# ADDITIONAL.net
KiCad netlist of a schematic drawn in Altium Designer
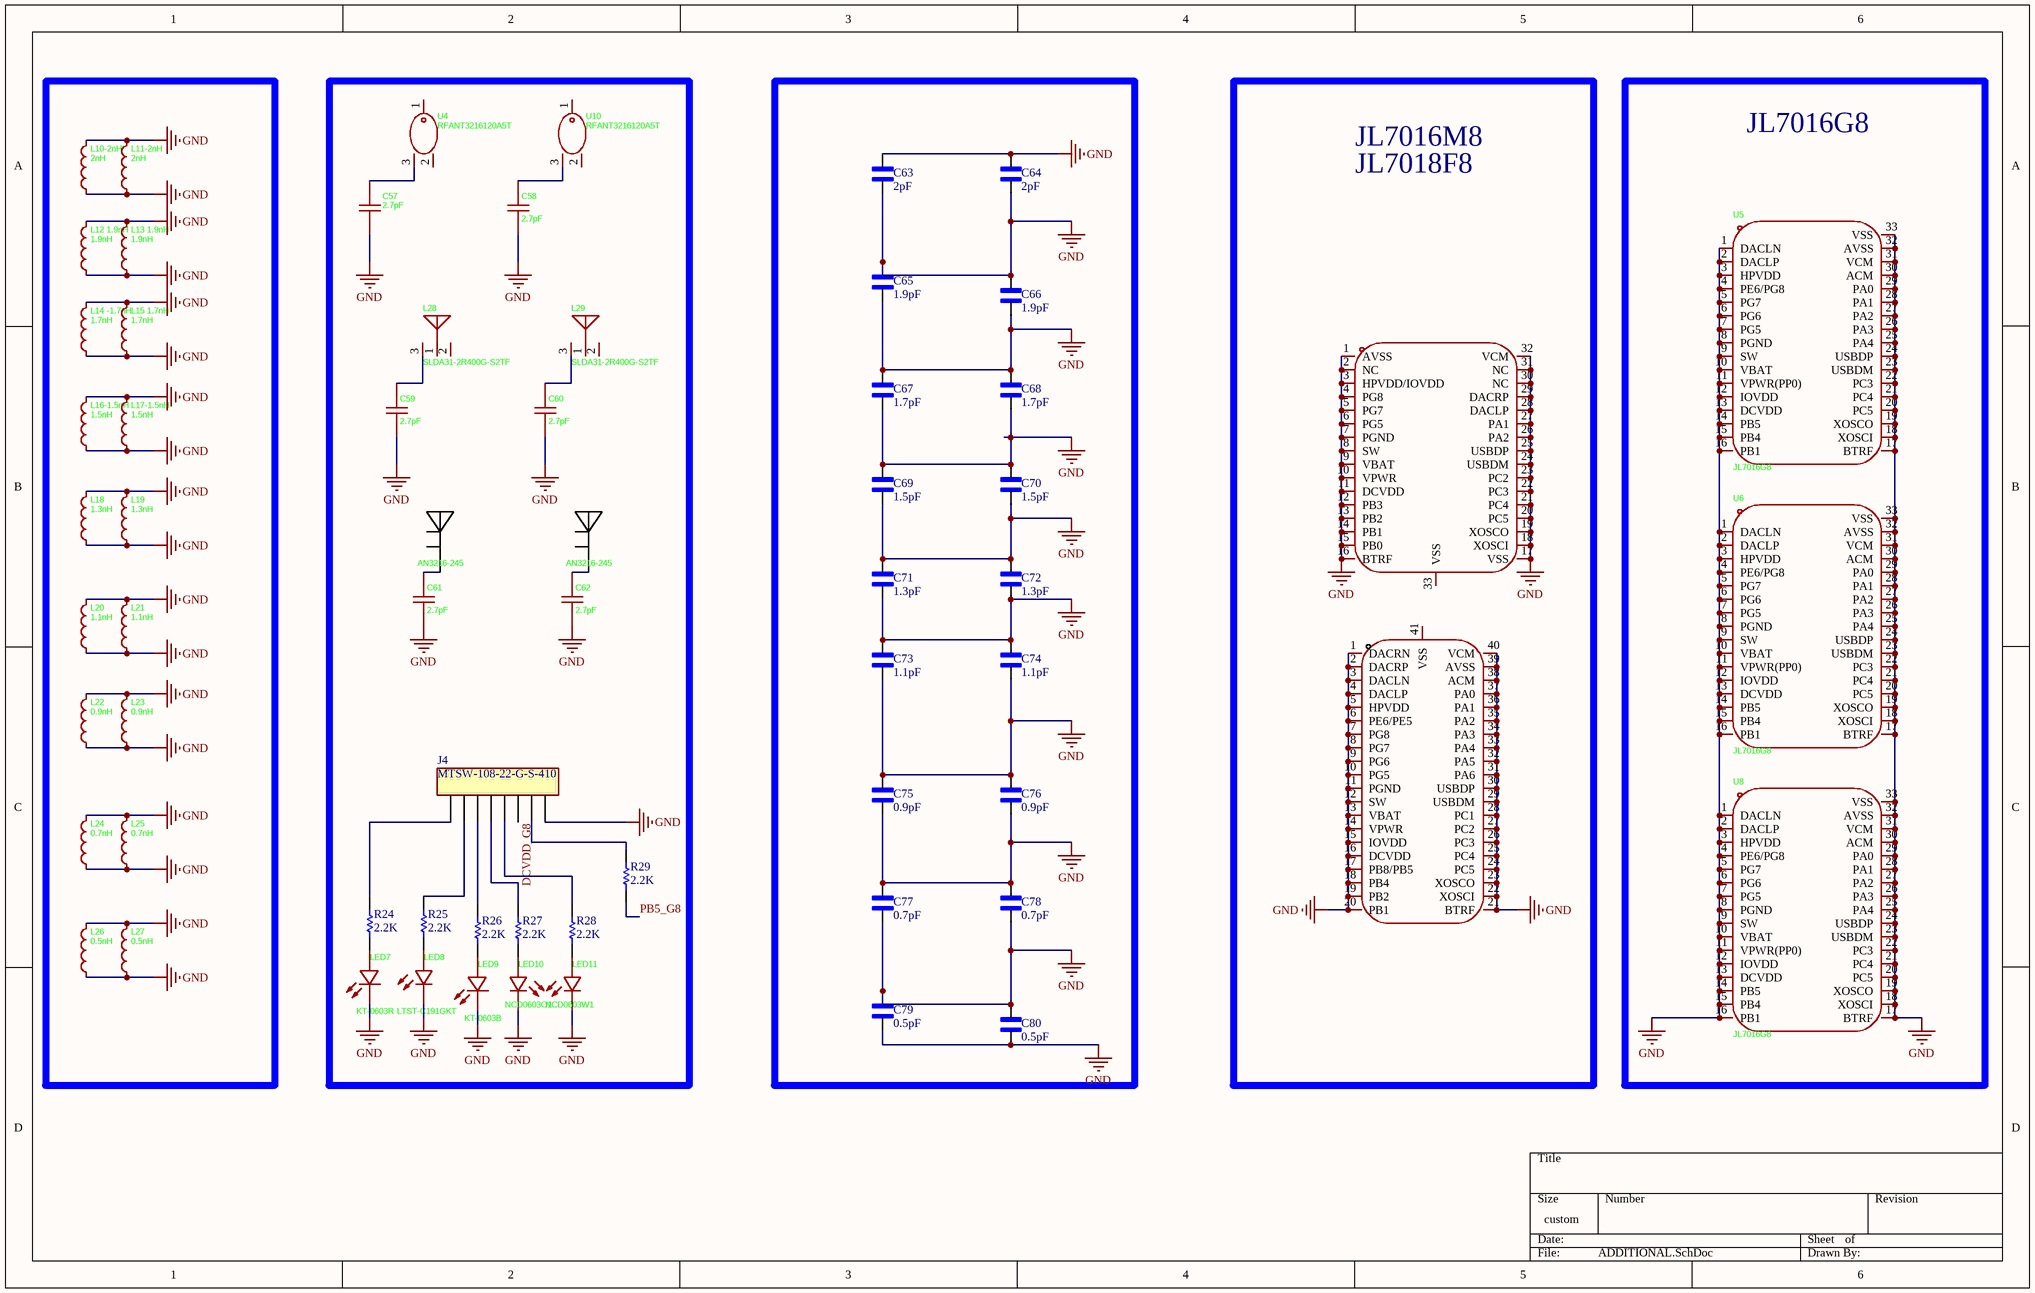
[diagram p0: ADDITIONAL.SchDoc]

(export (version "E")
  (design (tool "Eeschema 10.0.6"))
  (components
    (comp (ref "ANT4")
      (value "AN3216-245")
      (footprint "CUSTOME ANTEENA")
      (fields (field (name "MANUFACTURER") "Rainsun(霖昱微)") (field (name "POWER") "1W"))
      (libsource (lib "JEILI_DEV_BOARD") (part "AN3216-245"))
    )
    (comp (ref "ANT5")
      (value "AN3216-245")
      (footprint "CUSTOME ANTEENA")
      (fields (field (name "MANUFACTURER") "Rainsun(霖昱微)") (field (name "POWER") "1W"))
      (libsource (lib "JEILI_DEV_BOARD") (part "AN3216-245"))
    )
    (comp (ref "C57")
      (value "2.7pF")
      (footprint "C0603")
      (fields (field (name "MANUFACTURER") "FH(风华)") (field (name "MANUFACTURER PART") "0603CG2R7C500NT"))
      (libsource (lib "JEILI_DEV_BOARD") (part "0603CG2R7C500NT"))
    )
    (comp (ref "C58")
      (value "2.7pF")
      (footprint "C0603")
      (fields (field (name "MANUFACTURER") "FH(风华)") (field (name "MANUFACTURER PART") "0603CG2R7C500NT"))
      (libsource (lib "JEILI_DEV_BOARD") (part "0603CG2R7C500NT"))
    )
    (comp (ref "C59")
      (value "2.7pF")
      (footprint "C0603")
      (fields (field (name "MANUFACTURER") "FH(风华)") (field (name "MANUFACTURER PART") "0603CG2R7C500NT"))
      (libsource (lib "JEILI_DEV_BOARD") (part "0603CG2R7C500NT"))
    )
    (comp (ref "C60")
      (value "2.7pF")
      (footprint "C0603")
      (fields (field (name "MANUFACTURER") "FH(风华)") (field (name "MANUFACTURER PART") "0603CG2R7C500NT"))
      (libsource (lib "JEILI_DEV_BOARD") (part "0603CG2R7C500NT"))
    )
    (comp (ref "C61")
      (value "2.7pF")
      (footprint "C0603")
      (fields (field (name "MANUFACTURER") "FH(风华)") (field (name "MANUFACTURER PART") "0603CG2R7C500NT"))
      (libsource (lib "JEILI_DEV_BOARD") (part "0603CG2R7C500NT"))
    )
    (comp (ref "C62")
      (value "2.7pF")
      (footprint "C0603")
      (fields (field (name "MANUFACTURER") "FH(风华)") (field (name "MANUFACTURER PART") "0603CG2R7C500NT"))
      (libsource (lib "JEILI_DEV_BOARD") (part "0603CG2R7C500NT"))
    )
    (comp (ref "C63")
      (value "2pF")
      (footprint "C0402")
      (description "2pF 50V C0G 0402 Multilayer Ceramic Capacitors MLCC - SMD/SMT ROHS")
      (fields
        (field (name "MANUFACTURER") "Murata Electronics")
        (field (name "MFR.PART #") "GJM1555C1H2R0WB01D")
      )
      (libsource (lib "JEILI_DEV_BOARD") (part "CAP 2pF"))
    )
    (comp (ref "C64")
      (value "2pF")
      (footprint "C0402")
      (description "2pF 50V C0G 0402 Multilayer Ceramic Capacitors MLCC - SMD/SMT ROHS")
      (fields
        (field (name "MANUFACTURER") "Murata Electronics")
        (field (name "MFR.PART #") "GJM1555C1H2R0WB01D")
      )
      (libsource (lib "JEILI_DEV_BOARD") (part "CAP 2pF"))
    )
    (comp (ref "C65")
      (value "1.9pF")
      (footprint "C0402")
      (description "1.9pF 50V C0G 0402 Multilayer Ceramic Capacitors MLCC - SMD/SMT ROHS")
      (fields
        (field (name "MANUFACTURER") "Murata Electronics")
        (field (name "MFR.PART #") "GJM1555C1H1R9BB01D")
      )
      (libsource (lib "JEILI_DEV_BOARD") (part "CAP 1.9pF"))
    )
    (comp (ref "C66")
      (value "1.9pF")
      (footprint "C0402")
      (description "1.9pF 50V C0G 0402 Multilayer Ceramic Capacitors MLCC - SMD/SMT ROHS")
      (fields
        (field (name "MANUFACTURER") "Murata Electronics")
        (field (name "MFR.PART #") "GJM1555C1H1R9BB01D")
      )
      (libsource (lib "JEILI_DEV_BOARD") (part "CAP 1.9pF"))
    )
    (comp (ref "C67")
      (value "1.7pF")
      (footprint "C0402")
      (description "1.7pF 50V C0G 0402 Multilayer Ceramic Capacitors MLCC - SMD/SMT ROHS")
      (fields
        (field (name "MANUFACTURER") "Murata Electronics")
        (field (name "MFR.PART #") "GJM1555C1H1R7WB01D")
      )
      (libsource (lib "JEILI_DEV_BOARD") (part "CAP 1.7pF"))
    )
    (comp (ref "C68")
      (value "1.7pF")
      (footprint "C0402")
      (description "1.7pF 50V C0G 0402 Multilayer Ceramic Capacitors MLCC - SMD/SMT ROHS")
      (fields
        (field (name "MANUFACTURER") "Murata Electronics")
        (field (name "MFR.PART #") "GJM1555C1H1R7WB01D")
      )
      (libsource (lib "JEILI_DEV_BOARD") (part "CAP 1.7pF"))
    )
    (comp (ref "C69")
      (value "1.5pF")
      (footprint "C0402")
      (description "1.5pF 50V C0G 0402 Multilayer Ceramic Capacitors MLCC - SMD/SMT ROHS")
      (fields
        (field (name "MANUFACTURER") "Murata Electronics")
        (field (name "MFR.PART #") "GJM1555C1H1R5BB01D")
      )
      (libsource (lib "JEILI_DEV_BOARD") (part "CAP 1.5pF"))
    )
    (comp (ref "C70")
      (value "1.5pF")
      (footprint "C0402")
      (description "1.5pF 50V C0G 0402 Multilayer Ceramic Capacitors MLCC - SMD/SMT ROHS")
      (fields
        (field (name "MANUFACTURER") "Murata Electronics")
        (field (name "MFR.PART #") "GJM1555C1H1R5BB01D")
      )
      (libsource (lib "JEILI_DEV_BOARD") (part "CAP 1.5pF"))
    )
    (comp (ref "C71")
      (value "1.3pF")
      (footprint "C0402")
      (description "1.3pF 50V C0G 0402 Multilayer Ceramic Capacitors MLCC - SMD/SMT ROHS")
      (fields
        (field (name "MANUFACTURER") "Murata Electronics")
        (field (name "MFR.PART #") "GJM1555C1H1R3WB01D")
      )
      (libsource (lib "JEILI_DEV_BOARD") (part "CAP 1.3pF"))
    )
    (comp (ref "C72")
      (value "1.3pF")
      (footprint "C0402")
      (description "1.3pF 50V C0G 0402 Multilayer Ceramic Capacitors MLCC - SMD/SMT ROHS")
      (fields
        (field (name "MANUFACTURER") "Murata Electronics")
        (field (name "MFR.PART #") "GJM1555C1H1R3WB01D")
      )
      (libsource (lib "JEILI_DEV_BOARD") (part "CAP 1.3pF"))
    )
    (comp (ref "C73")
      (value "1.1pF")
      (footprint "C0402")
      (description "1.1pF 50V C0G 0402 Multilayer Ceramic Capacitors MLCC - SMD/SMT ROHS")
      (fields
        (field (name "MANUFACTURER") "Murata Electronics")
        (field (name "MFR.PART #") "GJM1555C1H1R1WB01D")
      )
      (libsource (lib "JEILI_DEV_BOARD") (part "CAP 1.1pF"))
    )
    (comp (ref "C74")
      (value "1.1pF")
      (footprint "C0402")
      (description "1.1pF 50V C0G 0402 Multilayer Ceramic Capacitors MLCC - SMD/SMT ROHS")
      (fields
        (field (name "MANUFACTURER") "Murata Electronics")
        (field (name "MFR.PART #") "GJM1555C1H1R1WB01D")
      )
      (libsource (lib "JEILI_DEV_BOARD") (part "CAP 1.1pF"))
    )
    (comp (ref "C75")
      (value "0.9pF")
      (footprint "C0402")
      (description "0.9pF 50V C0G 0402 Multilayer Ceramic Capacitors MLCC - SMD/SMT ROHS")
      (fields
        (field (name "MANUFACTURER") "FH (Guangdong Fenghua Advanced Tech)")
        (field (name "MFR.PART #") "0402CG0R9B500NT")
      )
      (libsource (lib "JEILI_DEV_BOARD") (part "CAP 0.9pF"))
    )
    (comp (ref "C76")
      (value "0.9pF")
      (footprint "C0402")
      (description "0.9pF 50V C0G 0402 Multilayer Ceramic Capacitors MLCC - SMD/SMT ROHS")
      (fields
        (field (name "MANUFACTURER") "FH (Guangdong Fenghua Advanced Tech)")
        (field (name "MFR.PART #") "0402CG0R9B500NT")
      )
      (libsource (lib "JEILI_DEV_BOARD") (part "CAP 0.9pF"))
    )
    (comp (ref "C77")
      (value "0.7pF")
      (footprint "C0402")
      (description "0.7pF 50V C0G 0402 Multilayer Ceramic Capacitors MLCC - SMD/SMT ROHS")
      (fields
        (field (name "MANUFACTURER") "FH (Guangdong Fenghua Advanced Tech)")
        (field (name "MFR.PART #") "0402CG0R7C500NT")
      )
      (libsource (lib "JEILI_DEV_BOARD") (part "CAP 0.7pF"))
    )
    (comp (ref "C78")
      (value "0.7pF")
      (footprint "C0402")
      (description "0.7pF 50V C0G 0402 Multilayer Ceramic Capacitors MLCC - SMD/SMT ROHS")
      (fields
        (field (name "MANUFACTURER") "FH (Guangdong Fenghua Advanced Tech)")
        (field (name "MFR.PART #") "0402CG0R7C500NT")
      )
      (libsource (lib "JEILI_DEV_BOARD") (part "CAP 0.7pF"))
    )
    (comp (ref "C79")
      (value "0.5pF")
      (footprint "C0402")
      (description "0.5pF 50V C0G 0402 Multilayer Ceramic Capacitors MLCC - SMD/SMT ROHS")
      (fields
        (field (name "MANUFACTURER") "FH (Guangdong Fenghua Advanced Tech)")
        (field (name "MFR.PART #") "0402CG0R5C500NT")
      )
      (libsource (lib "JEILI_DEV_BOARD") (part "CAP 0.5pF"))
    )
    (comp (ref "C80")
      (value "0.5pF")
      (footprint "C0402")
      (description "0.5pF 50V C0G 0402 Multilayer Ceramic Capacitors MLCC - SMD/SMT ROHS")
      (fields
        (field (name "MANUFACTURER") "FH (Guangdong Fenghua Advanced Tech)")
        (field (name "MFR.PART #") "0402CG0R5C500NT")
      )
      (libsource (lib "JEILI_DEV_BOARD") (part "CAP 0.5pF"))
    )
    (comp (ref "J4")
      (value "MTSW-108-22-G-S-410")
      (footprint "SAMTEC_MTSW-108-22-G-S-410")
      (libsource (lib "JEILI_DEV_BOARD") (part "MTSW-108-22-G-S-410"))
    )
    (comp (ref "L10-2nH")
      (value "2nH")
      (footprint "L0603")
      (description "2nH Multilayer inductor 0603 Inductors (SMD) ROHS")
      (fields
        (field (name "MANUFACTURER") "Murata Electronics")
        (field (name "MANUFACTURER PART") "SDCL1608C2N0STDF")
      )
      (libsource (lib "JEILI_DEV_BOARD") (part "2nH"))
    )
    (comp (ref "L11-2nH")
      (value "2nH")
      (footprint "L0603")
      (description "2nH Multilayer inductor 0603 Inductors (SMD) ROHS")
      (fields
        (field (name "MANUFACTURER") "Murata Electronics")
        (field (name "MANUFACTURER PART") "SDCL1608C2N0STDF")
      )
      (libsource (lib "JEILI_DEV_BOARD") (part "2nH"))
    )
    (comp (ref "L12 1.9nH")
      (value "1.9nH")
      (footprint "L0603")
      (description "1.04A 1.9nH 11.3MHz 16@250MHz 70mΩ 0402 Inductors (SMD) ROHS")
      (fields
        (field (name "MANUFACTURER") "Chilisin Elec")
        (field (name "MANUFACTURER PART") "CS0402-1N9B-S")
      )
      (libsource (lib "JEILI_DEV_BOARD") (part "1.9nH"))
    )
    (comp (ref "L13 1.9nH")
      (value "1.9nH")
      (footprint "L0603")
      (description "1.04A 1.9nH 11.3MHz 16@250MHz 70mΩ 0402 Inductors (SMD) ROHS")
      (fields
        (field (name "MANUFACTURER") "Chilisin Elec")
        (field (name "MANUFACTURER PART") "CS0402-1N9B-S")
      )
      (libsource (lib "JEILI_DEV_BOARD") (part "1.9nH"))
    )
    (comp (ref "L14 -1.7nH")
      (value "1.7nH")
      (footprint "L0603")
      (description "1.7nH 100mΩ 640mA 0402 Inductors (SMD) ROHS")
      (fields (field (name "MANUFACTURER") "Sunlord") (field (name "MANUFACTURER PART") "MWSD1005C1N7STM01"))
      (libsource (lib "JEILI_DEV_BOARD") (part "1.7nH"))
    )
    (comp (ref "L15 1.7nH")
      (value "1.7nH")
      (footprint "L0603")
      (description "1.7nH 100mΩ 640mA 0402 Inductors (SMD) ROHS")
      (fields (field (name "MANUFACTURER") "Sunlord") (field (name "MANUFACTURER PART") "MWSD1005C1N7STM01"))
      (libsource (lib "JEILI_DEV_BOARD") (part "1.7nH"))
    )
    (comp (ref "L16-1.5nH")
      (value "1.5nH")
      (footprint "L0603")
      (description "1.5nH 100mΩ 500mA 6GHz 8@100MHz Multilayer inductor 0603 Inductors (SMD) ROHS")
      (fields (field (name "MANUFACTURER") "Sunlord") (field (name "MANUFACTURER PART") "SDCL1608C1N5STDF"))
      (libsource (lib "JEILI_DEV_BOARD") (part "1.5nH"))
    )
    (comp (ref "L17-1.5nH")
      (value "1.5nH")
      (footprint "L0603")
      (description "1.5nH 100mΩ 500mA 6GHz 8@100MHz Multilayer inductor 0603 Inductors (SMD) ROHS")
      (fields (field (name "MANUFACTURER") "Sunlord") (field (name "MANUFACTURER PART") "SDCL1608C1N5STDF"))
      (libsource (lib "JEILI_DEV_BOARD") (part "1.5nH"))
    )
    (comp (ref "L18")
      (value "1.3nH")
      (footprint "L0603")
      (description "1.3nH 1A 40mΩ 7@100MHz 8GHz Multilayer inductor 0402 Inductors (SMD) ROHS")
      (fields (field (name "MANUFACTURER") "TDK") (field (name "MANUFACTURER PART") "MLG1005S1N3BT000"))
      (libsource (lib "JEILI_DEV_BOARD") (part "1.3nH"))
    )
    (comp (ref "L19")
      (value "1.3nH")
      (footprint "L0603")
      (description "1.3nH 1A 40mΩ 7@100MHz 8GHz Multilayer inductor 0402 Inductors (SMD) ROHS")
      (fields (field (name "MANUFACTURER") "TDK") (field (name "MANUFACTURER PART") "MLG1005S1N3BT000"))
      (libsource (lib "JEILI_DEV_BOARD") (part "1.3nH"))
    )
    (comp (ref "L20")
      (value "1.1nH")
      (footprint "L0603")
      (description "1.1nH 10GHz 1A 30mΩ 7@100MHz AEC-Q200 Multilayer inductor 0402 Inductors (SMD) ROHS")
      (fields (field (name "MANUFACTURER") "TDK") (field (name "MANUFACTURER PART") "MLG1005S1N1BTD25"))
      (libsource (lib "JEILI_DEV_BOARD") (part "1.1nH"))
    )
    (comp (ref "L21")
      (value "1.1nH")
      (footprint "L0603")
      (description "1.1nH 10GHz 1A 30mΩ 7@100MHz AEC-Q200 Multilayer inductor 0402 Inductors (SMD) ROHS")
      (fields (field (name "MANUFACTURER") "TDK") (field (name "MANUFACTURER PART") "MLG1005S1N1BTD25"))
      (libsource (lib "JEILI_DEV_BOARD") (part "1.1nH"))
    )
    (comp (ref "L22")
      (value "0.9nH")
      (footprint "L0603")
      (description "0.9nH 100mΩ 10GHz 1A Multilayer inductor 0402 Inductors (SMD) ROHS")
      (fields (field (name "MANUFACTURER") "TDK") (field (name "MANUFACTURER PART") "MLG1005S0N9BT000"))
      (libsource (lib "JEILI_DEV_BOARD") (part "0.9nH"))
    )
    (comp (ref "L23")
      (value "0.9nH")
      (footprint "L0603")
      (description "0.9nH 100mΩ 10GHz 1A Multilayer inductor 0402 Inductors (SMD) ROHS")
      (fields (field (name "MANUFACTURER") "TDK") (field (name "MANUFACTURER PART") "MLG1005S0N9BT000"))
      (libsource (lib "JEILI_DEV_BOARD") (part "0.9nH"))
    )
    (comp (ref "L24")
      (value "0.7nH")
      (footprint "L0603")
      (description "0.7nH 100mΩ 10GHz 1A Multilayer inductor 0402 Inductors (SMD) ROHS")
      (fields (field (name "MANUFACTURER") "TDK") (field (name "MANUFACTURER PART") "MLG1005S0N7BT000"))
      (libsource (lib "JEILI_DEV_BOARD") (part "0.7nH"))
    )
    (comp (ref "L25")
      (value "0.7nH")
      (footprint "L0603")
      (description "0.7nH 100mΩ 10GHz 1A Multilayer inductor 0402 Inductors (SMD) ROHS")
      (fields (field (name "MANUFACTURER") "TDK") (field (name "MANUFACTURER PART") "MLG1005S0N7BT000"))
      (libsource (lib "JEILI_DEV_BOARD") (part "0.7nH"))
    )
    (comp (ref "L26")
      (value "0.5nH")
      (footprint "L0603")
      (description "0.5nH 100mΩ 10GHz 1A Multilayer inductor 0402 Inductors (SMD) ROHS")
      (fields (field (name "MANUFACTURER") "TDK") (field (name "MANUFACTURER PART") "MLG1005S0N5BT000"))
      (libsource (lib "JEILI_DEV_BOARD") (part "0.5nH"))
    )
    (comp (ref "L27")
      (value "0.5nH")
      (footprint "L0603")
      (description "0.5nH 100mΩ 10GHz 1A Multilayer inductor 0402 Inductors (SMD) ROHS")
      (fields (field (name "MANUFACTURER") "TDK") (field (name "MANUFACTURER PART") "MLG1005S0N5BT000"))
      (libsource (lib "JEILI_DEV_BOARD") (part "0.5nH"))
    )
    (comp (ref "L28")
      (value "SLDA31-2R400G-S2TF")
      (footprint "CUSTOME ANTEENA")
      (fields (field (name "MANUFACTURER") "Sunlord(顺络)") (field (name "POWER") "3W"))
      (libsource (lib "JEILI_DEV_BOARD") (part "SLDA31-2R400G-S2TF"))
    )
    (comp (ref "L29")
      (value "SLDA31-2R400G-S2TF")
      (footprint "CUSTOME ANTEENA")
      (fields (field (name "MANUFACTURER") "Sunlord(顺络)") (field (name "POWER") "3W"))
      (libsource (lib "JEILI_DEV_BOARD") (part "SLDA31-2R400G-S2TF"))
    )
    (comp (ref "LED7")
      (value "KT-0603R")
      (footprint "LED0603-RD")
      (fields (field (name "MANUFACTURER") "KENTO"))
      (libsource (lib "JEILI_DEV_BOARD") (part "KT-0603R"))
    )
    (comp (ref "LED8")
      (value "LTST-C191GKT")
      (footprint "LED0603-R-RD_GREEN")
      (fields (field (name "MANUFACTURER") "LITEON(光宝)"))
      (libsource (lib "JEILI_DEV_BOARD") (part "LTST-C191GKT"))
    )
    (comp (ref "LED9")
      (value "KT-0603B")
      (footprint "LED0603-RD")
      (fields (field (name "MANUFACTURER") "KENTO"))
      (libsource (lib "JEILI_DEV_BOARD") (part "KT-0603B"))
    )
    (comp (ref "LED10")
      (value "NCD0603O1")
      (footprint "LED0603-RD")
      (fields (field (name "MANUFACTURER") "国星光电"))
      (libsource (lib "JEILI_DEV_BOARD") (part "NCD0603O1"))
    )
    (comp (ref "LED11")
      (value "NCD0603W1")
      (footprint "LED0603-RD")
      (fields (field (name "MANUFACTURER") "国星光电"))
      (libsource (lib "JEILI_DEV_BOARD") (part "NCD0603W1"))
    )
    (comp (ref "R24")
      (value "2.2K")
      (footprint "R0603")
      (fields
        (field (name "MANUFACTURER") "YAGEO")
        (field (name "MFR.PART #") "RC0402JR-0733RL")
        (field (name "JLCPCB PART #") "C137880")
      )
      (libsource (lib "JEILI_DEV_BOARD") (part "RES_2.2K"))
    )
    (comp (ref "R25")
      (value "2.2K")
      (footprint "R0603")
      (fields
        (field (name "MANUFACTURER") "YAGEO")
        (field (name "MFR.PART #") "RC0402JR-0733RL")
        (field (name "JLCPCB PART #") "C137880")
      )
      (libsource (lib "JEILI_DEV_BOARD") (part "RES_2.2K"))
    )
    (comp (ref "R26")
      (value "2.2K")
      (footprint "R0603")
      (fields
        (field (name "MANUFACTURER") "YAGEO")
        (field (name "MFR.PART #") "RC0402JR-0733RL")
        (field (name "JLCPCB PART #") "C137880")
      )
      (libsource (lib "JEILI_DEV_BOARD") (part "RES_2.2K"))
    )
    (comp (ref "R27")
      (value "2.2K")
      (footprint "R0603")
      (fields
        (field (name "MANUFACTURER") "YAGEO")
        (field (name "MFR.PART #") "RC0402JR-0733RL")
        (field (name "JLCPCB PART #") "C137880")
      )
      (libsource (lib "JEILI_DEV_BOARD") (part "RES_2.2K"))
    )
    (comp (ref "R28")
      (value "2.2K")
      (footprint "R0603")
      (fields
        (field (name "MANUFACTURER") "YAGEO")
        (field (name "MFR.PART #") "RC0402JR-0733RL")
        (field (name "JLCPCB PART #") "C137880")
      )
      (libsource (lib "JEILI_DEV_BOARD") (part "RES_2.2K"))
    )
    (comp (ref "R29")
      (value "2.2K")
      (footprint "R0603")
      (fields
        (field (name "MANUFACTURER") "YAGEO")
        (field (name "MFR.PART #") "RC0402JR-0733RL")
        (field (name "JLCPCB PART #") "C137880")
      )
      (libsource (lib "JEILI_DEV_BOARD") (part "RES_2.2K"))
    )
    (comp (ref "U4")
      (value "RFANT3216120A5T")
      (footprint "CUSTOME ANTEENA")
      (fields (field (name "MANUFACTURER") "Walsin(华新科)"))
      (libsource (lib "JEILI_DEV_BOARD") (part "RFANT3216120A5T"))
    )
    (comp (ref "U5")
      (value "JL7016G8")
      (footprint "QFN-32_L4.0-W4.0-P0.40-TL-EP2.7")
      (fields (field (name "MANUFACTURER") "JL(杰理)"))
      (libsource (lib "JEILI_DEV_BOARD") (part "JL7016G8"))
    )
    (comp (ref "U6")
      (value "JL7016G8")
      (footprint "QFN-32_L4.0-W4.0-P0.40-TL-EP2.7")
      (fields (field (name "MANUFACTURER") "JL(杰理)"))
      (libsource (lib "JEILI_DEV_BOARD") (part "JL7016G8"))
    )
    (comp (ref "U7")
      (value "JL7016M8")
      (footprint "QFN-32_L4.0-W4.0-P0.40-TL-EP2.7_1")
      (fields (field (name "MANUFACTURER") "JL(杰理)"))
      (libsource (lib "JEILI_DEV_BOARD") (part "JL7016M8"))
    )
    (comp (ref "U8")
      (value "JL7016G8")
      (footprint "QFN-32_L4.0-W4.0-P0.40-TL-EP2.7")
      (fields (field (name "MANUFACTURER") "JL(杰理)"))
      (libsource (lib "JEILI_DEV_BOARD") (part "JL7016G8"))
    )
    (comp (ref "U9")
      (value "JL7018F8")
      (footprint "QFN-40_L5.0-W5.0-P0.40-TL-EP3.6")
      (fields (field (name "MANUFACTURER") "JL(杰理)"))
      (libsource (lib "JEILI_DEV_BOARD") (part "JL7018F8"))
    )
    (comp (ref "U10")
      (value "RFANT3216120A5T")
      (footprint "CUSTOME ANTEENA")
      (fields (field (name "MANUFACTURER") "Walsin(华新科)"))
      (libsource (lib "JEILI_DEV_BOARD") (part "RFANT3216120A5T"))
    )
  )
  (nets
    (net (code "1") (name "/DCVDD_G8") (class "Default")
      (node (ref "J4") (pin "06") (pinfunction "06_06") (pintype "passive"))
    )
    (net (code "2") (name "/PB5_G8") (class "Default")
      (node (ref "R29") (pin "1") (pinfunction "1_1") (pintype "passive"))
    )
    (net (code "3") (name "GND") (class "Default")
      (node (ref "C57") (pin "1") (pinfunction "1_1") (pintype "passive"))
      (node (ref "C58") (pin "1") (pinfunction "1_1") (pintype "passive"))
      (node (ref "C59") (pin "1") (pinfunction "1_1") (pintype "passive"))
      (node (ref "C60") (pin "1") (pinfunction "1_1") (pintype "passive"))
      (node (ref "C61") (pin "1") (pinfunction "1_1") (pintype "passive"))
      (node (ref "C62") (pin "1") (pinfunction "1_1") (pintype "passive"))
      (node (ref "C63") (pin "1") (pinfunction "1_1") (pintype "passive"))
      (node (ref "C63") (pin "2") (pinfunction "2_2") (pintype "passive"))
      (node (ref "C64") (pin "1") (pinfunction "1_1") (pintype "passive"))
      (node (ref "C64") (pin "2") (pinfunction "2_2") (pintype "passive"))
      (node (ref "C65") (pin "1") (pinfunction "1_1") (pintype "passive"))
      (node (ref "C65") (pin "2") (pinfunction "2_2") (pintype "passive"))
      (node (ref "C66") (pin "1") (pinfunction "1_1") (pintype "passive"))
      (node (ref "C66") (pin "2") (pinfunction "2_2") (pintype "passive"))
      (node (ref "C67") (pin "1") (pinfunction "1_1") (pintype "passive"))
      (node (ref "C67") (pin "2") (pinfunction "2_2") (pintype "passive"))
      (node (ref "C68") (pin "1") (pinfunction "1_1") (pintype "passive"))
      (node (ref "C68") (pin "2") (pinfunction "2_2") (pintype "passive"))
      (node (ref "C69") (pin "1") (pinfunction "1_1") (pintype "passive"))
      (node (ref "C69") (pin "2") (pinfunction "2_2") (pintype "passive"))
      (node (ref "C70") (pin "1") (pinfunction "1_1") (pintype "passive"))
      (node (ref "C70") (pin "2") (pinfunction "2_2") (pintype "passive"))
      (node (ref "C71") (pin "1") (pinfunction "1_1") (pintype "passive"))
      (node (ref "C71") (pin "2") (pinfunction "2_2") (pintype "passive"))
      (node (ref "C72") (pin "1") (pinfunction "1_1") (pintype "passive"))
      (node (ref "C72") (pin "2") (pinfunction "2_2") (pintype "passive"))
      (node (ref "C73") (pin "1") (pinfunction "1_1") (pintype "passive"))
      (node (ref "C73") (pin "2") (pinfunction "2_2") (pintype "passive"))
      (node (ref "C74") (pin "1") (pinfunction "1_1") (pintype "passive"))
      (node (ref "C74") (pin "2") (pinfunction "2_2") (pintype "passive"))
      (node (ref "C75") (pin "1") (pinfunction "1_1") (pintype "passive"))
      (node (ref "C75") (pin "2") (pinfunction "2_2") (pintype "passive"))
      (node (ref "C76") (pin "1") (pinfunction "1_1") (pintype "passive"))
      (node (ref "C76") (pin "2") (pinfunction "2_2") (pintype "passive"))
      (node (ref "C77") (pin "1") (pinfunction "1_1") (pintype "passive"))
      (node (ref "C77") (pin "2") (pinfunction "2_2") (pintype "passive"))
      (node (ref "C78") (pin "1") (pinfunction "1_1") (pintype "passive"))
      (node (ref "C78") (pin "2") (pinfunction "2_2") (pintype "passive"))
      (node (ref "C79") (pin "1") (pinfunction "1_1") (pintype "passive"))
      (node (ref "C79") (pin "2") (pinfunction "2_2") (pintype "passive"))
      (node (ref "C80") (pin "1") (pinfunction "1_1") (pintype "passive"))
      (node (ref "C80") (pin "2") (pinfunction "2_2") (pintype "passive"))
      (node (ref "J4") (pin "08") (pinfunction "08_08") (pintype "passive"))
      (node (ref "L10-2nH") (pin "1") (pinfunction "1_1") (pintype "passive"))
      (node (ref "L10-2nH") (pin "2") (pinfunction "2_2") (pintype "passive"))
      (node (ref "L11-2nH") (pin "1") (pinfunction "1_1") (pintype "passive"))
      (node (ref "L11-2nH") (pin "2") (pinfunction "2_2") (pintype "passive"))
      (node (ref "L12 1.9nH") (pin "1") (pinfunction "1_1") (pintype "passive"))
      (node (ref "L12 1.9nH") (pin "2") (pinfunction "2_2") (pintype "passive"))
      (node (ref "L13 1.9nH") (pin "1") (pinfunction "1_1") (pintype "passive"))
      (node (ref "L13 1.9nH") (pin "2") (pinfunction "2_2") (pintype "passive"))
      (node (ref "L14 -1.7nH") (pin "1") (pinfunction "1_1") (pintype "passive"))
      (node (ref "L14 -1.7nH") (pin "2") (pinfunction "2_2") (pintype "passive"))
      (node (ref "L15 1.7nH") (pin "1") (pinfunction "1_1") (pintype "passive"))
      (node (ref "L15 1.7nH") (pin "2") (pinfunction "2_2") (pintype "passive"))
      (node (ref "L16-1.5nH") (pin "1") (pinfunction "1_1") (pintype "passive"))
      (node (ref "L16-1.5nH") (pin "2") (pinfunction "2_2") (pintype "passive"))
      (node (ref "L17-1.5nH") (pin "1") (pinfunction "1_1") (pintype "passive"))
      (node (ref "L17-1.5nH") (pin "2") (pinfunction "2_2") (pintype "passive"))
      (node (ref "L18") (pin "1") (pinfunction "1_1") (pintype "passive"))
      (node (ref "L18") (pin "2") (pinfunction "2_2") (pintype "passive"))
      (node (ref "L19") (pin "1") (pinfunction "1_1") (pintype "passive"))
      (node (ref "L19") (pin "2") (pinfunction "2_2") (pintype "passive"))
      (node (ref "L20") (pin "1") (pinfunction "1_1") (pintype "passive"))
      (node (ref "L20") (pin "2") (pinfunction "2_2") (pintype "passive"))
      (node (ref "L21") (pin "1") (pinfunction "1_1") (pintype "passive"))
      (node (ref "L21") (pin "2") (pinfunction "2_2") (pintype "passive"))
      (node (ref "L22") (pin "1") (pinfunction "1_1") (pintype "passive"))
      (node (ref "L22") (pin "2") (pinfunction "2_2") (pintype "passive"))
      (node (ref "L23") (pin "1") (pinfunction "1_1") (pintype "passive"))
      (node (ref "L23") (pin "2") (pinfunction "2_2") (pintype "passive"))
      (node (ref "L24") (pin "1") (pinfunction "1_1") (pintype "passive"))
      (node (ref "L24") (pin "2") (pinfunction "2_2") (pintype "passive"))
      (node (ref "L25") (pin "1") (pinfunction "1_1") (pintype "passive"))
      (node (ref "L25") (pin "2") (pinfunction "2_2") (pintype "passive"))
      (node (ref "L26") (pin "1") (pinfunction "1_1") (pintype "passive"))
      (node (ref "L26") (pin "2") (pinfunction "2_2") (pintype "passive"))
      (node (ref "L27") (pin "1") (pinfunction "1_1") (pintype "passive"))
      (node (ref "L27") (pin "2") (pinfunction "2_2") (pintype "passive"))
      (node (ref "LED10") (pin "1") (pinfunction "K_1") (pintype "passive"))
      (node (ref "LED11") (pin "1") (pinfunction "-_1") (pintype "passive"))
      (node (ref "LED7") (pin "1") (pinfunction "K_1") (pintype "passive"))
      (node (ref "LED8") (pin "2") (pinfunction "C_2") (pintype "passive"))
      (node (ref "LED9") (pin "1") (pinfunction "K_1") (pintype "passive"))
      (node (ref "U5") (pin "1") (pinfunction "DACLN_1") (pintype "passive"))
      (node (ref "U5") (pin "10") (pinfunction "VBAT_10") (pintype "passive"))
      (node (ref "U5") (pin "11") (pinfunction "VPWR(PP0)_11") (pintype "passive"))
      (node (ref "U5") (pin "12") (pinfunction "IOVDD_12") (pintype "passive"))
      (node (ref "U5") (pin "13") (pinfunction "DCVDD_13") (pintype "passive"))
      (node (ref "U5") (pin "14") (pinfunction "PB5_14") (pintype "passive"))
      (node (ref "U5") (pin "15") (pinfunction "PB4_15") (pintype "passive"))
      (node (ref "U5") (pin "16") (pinfunction "PB1_16") (pintype "passive"))
      (node (ref "U5") (pin "17") (pinfunction "BTRF_17") (pintype "passive"))
      (node (ref "U5") (pin "18") (pinfunction "XOSCI_18") (pintype "passive"))
      (node (ref "U5") (pin "19") (pinfunction "XOSCO_19") (pintype "passive"))
      (node (ref "U5") (pin "2") (pinfunction "DACLP_2") (pintype "passive"))
      (node (ref "U5") (pin "20") (pinfunction "PC5_20") (pintype "passive"))
      (node (ref "U5") (pin "21") (pinfunction "PC4_21") (pintype "passive"))
      (node (ref "U5") (pin "22") (pinfunction "PC3_22") (pintype "passive"))
      (node (ref "U5") (pin "23") (pinfunction "USBDM_23") (pintype "passive"))
      (node (ref "U5") (pin "24") (pinfunction "USBDP_24") (pintype "passive"))
      (node (ref "U5") (pin "25") (pinfunction "PA4_25") (pintype "passive"))
      (node (ref "U5") (pin "26") (pinfunction "PA3_26") (pintype "passive"))
      (node (ref "U5") (pin "27") (pinfunction "PA2_27") (pintype "passive"))
      (node (ref "U5") (pin "28") (pinfunction "PA1_28") (pintype "passive"))
      (node (ref "U5") (pin "29") (pinfunction "PA0_29") (pintype "passive"))
      (node (ref "U5") (pin "3") (pinfunction "HPVDD_3") (pintype "passive"))
      (node (ref "U5") (pin "30") (pinfunction "ACM_30") (pintype "passive"))
      (node (ref "U5") (pin "31") (pinfunction "VCM_31") (pintype "passive"))
      (node (ref "U5") (pin "32") (pinfunction "AVSS_32") (pintype "passive"))
      (node (ref "U5") (pin "33") (pinfunction "VSS_33") (pintype "passive"))
      (node (ref "U5") (pin "4") (pinfunction "PE6/PG8_4") (pintype "passive"))
      (node (ref "U5") (pin "5") (pinfunction "PG7_5") (pintype "passive"))
      (node (ref "U5") (pin "6") (pinfunction "PG6_6") (pintype "passive"))
      (node (ref "U5") (pin "7") (pinfunction "PG5_7") (pintype "passive"))
      (node (ref "U5") (pin "8") (pinfunction "PGND_8") (pintype "passive"))
      (node (ref "U5") (pin "9") (pinfunction "SW_9") (pintype "passive"))
      (node (ref "U6") (pin "1") (pinfunction "DACLN_1") (pintype "passive"))
      (node (ref "U6") (pin "10") (pinfunction "VBAT_10") (pintype "passive"))
      (node (ref "U6") (pin "11") (pinfunction "VPWR(PP0)_11") (pintype "passive"))
      (node (ref "U6") (pin "12") (pinfunction "IOVDD_12") (pintype "passive"))
      (node (ref "U6") (pin "13") (pinfunction "DCVDD_13") (pintype "passive"))
      (node (ref "U6") (pin "14") (pinfunction "PB5_14") (pintype "passive"))
      (node (ref "U6") (pin "15") (pinfunction "PB4_15") (pintype "passive"))
      (node (ref "U6") (pin "16") (pinfunction "PB1_16") (pintype "passive"))
      (node (ref "U6") (pin "17") (pinfunction "BTRF_17") (pintype "passive"))
      (node (ref "U6") (pin "18") (pinfunction "XOSCI_18") (pintype "passive"))
      (node (ref "U6") (pin "19") (pinfunction "XOSCO_19") (pintype "passive"))
      (node (ref "U6") (pin "2") (pinfunction "DACLP_2") (pintype "passive"))
      (node (ref "U6") (pin "20") (pinfunction "PC5_20") (pintype "passive"))
      (node (ref "U6") (pin "21") (pinfunction "PC4_21") (pintype "passive"))
      (node (ref "U6") (pin "22") (pinfunction "PC3_22") (pintype "passive"))
      (node (ref "U6") (pin "23") (pinfunction "USBDM_23") (pintype "passive"))
      (node (ref "U6") (pin "24") (pinfunction "USBDP_24") (pintype "passive"))
      (node (ref "U6") (pin "25") (pinfunction "PA4_25") (pintype "passive"))
      (node (ref "U6") (pin "26") (pinfunction "PA3_26") (pintype "passive"))
      (node (ref "U6") (pin "27") (pinfunction "PA2_27") (pintype "passive"))
      (node (ref "U6") (pin "28") (pinfunction "PA1_28") (pintype "passive"))
      (node (ref "U6") (pin "29") (pinfunction "PA0_29") (pintype "passive"))
      (node (ref "U6") (pin "3") (pinfunction "HPVDD_3") (pintype "passive"))
      (node (ref "U6") (pin "30") (pinfunction "ACM_30") (pintype "passive"))
      (node (ref "U6") (pin "31") (pinfunction "VCM_31") (pintype "passive"))
      (node (ref "U6") (pin "32") (pinfunction "AVSS_32") (pintype "passive"))
      (node (ref "U6") (pin "33") (pinfunction "VSS_33") (pintype "passive"))
      (node (ref "U6") (pin "4") (pinfunction "PE6/PG8_4") (pintype "passive"))
      (node (ref "U6") (pin "5") (pinfunction "PG7_5") (pintype "passive"))
      (node (ref "U6") (pin "6") (pinfunction "PG6_6") (pintype "passive"))
      (node (ref "U6") (pin "7") (pinfunction "PG5_7") (pintype "passive"))
      (node (ref "U6") (pin "8") (pinfunction "PGND_8") (pintype "passive"))
      (node (ref "U6") (pin "9") (pinfunction "SW_9") (pintype "passive"))
      (node (ref "U7") (pin "1") (pinfunction "AVSS_1") (pintype "passive"))
      (node (ref "U7") (pin "10") (pinfunction "VPWR_10") (pintype "passive"))
      (node (ref "U7") (pin "11") (pinfunction "DCVDD_11") (pintype "passive"))
      (node (ref "U7") (pin "12") (pinfunction "PB3_12") (pintype "passive"))
      (node (ref "U7") (pin "13") (pinfunction "PB2_13") (pintype "passive"))
      (node (ref "U7") (pin "14") (pinfunction "PB1_14") (pintype "passive"))
      (node (ref "U7") (pin "15") (pinfunction "PB0_15") (pintype "passive"))
      (node (ref "U7") (pin "16") (pinfunction "BTRF_16") (pintype "passive"))
      (node (ref "U7") (pin "17") (pinfunction "VSS_17") (pintype "passive"))
      (node (ref "U7") (pin "18") (pinfunction "XOSCI_18") (pintype "passive"))
      (node (ref "U7") (pin "19") (pinfunction "XOSCO_19") (pintype "passive"))
      (node (ref "U7") (pin "2") (pinfunction "NC_2") (pintype "passive"))
      (node (ref "U7") (pin "20") (pinfunction "PC5_20") (pintype "passive"))
      (node (ref "U7") (pin "21") (pinfunction "PC4_21") (pintype "passive"))
      (node (ref "U7") (pin "22") (pinfunction "PC3_22") (pintype "passive"))
      (node (ref "U7") (pin "23") (pinfunction "PC2_23") (pintype "passive"))
      (node (ref "U7") (pin "24") (pinfunction "USBDM_24") (pintype "passive"))
      (node (ref "U7") (pin "25") (pinfunction "USBDP_25") (pintype "passive"))
      (node (ref "U7") (pin "26") (pinfunction "PA2_26") (pintype "passive"))
      (node (ref "U7") (pin "27") (pinfunction "PA1_27") (pintype "passive"))
      (node (ref "U7") (pin "28") (pinfunction "DACLP_28") (pintype "passive"))
      (node (ref "U7") (pin "29") (pinfunction "DACRP_29") (pintype "passive"))
      (node (ref "U7") (pin "3") (pinfunction "HPVDD/IOVDD_3") (pintype "passive"))
      (node (ref "U7") (pin "30") (pinfunction "NC_30") (pintype "passive"))
      (node (ref "U7") (pin "31") (pinfunction "NC_31") (pintype "passive"))
      (node (ref "U7") (pin "32") (pinfunction "VCM_32") (pintype "passive"))
      (node (ref "U7") (pin "4") (pinfunction "PG8_4") (pintype "passive"))
      (node (ref "U7") (pin "5") (pinfunction "PG7_5") (pintype "passive"))
      (node (ref "U7") (pin "6") (pinfunction "PG5_6") (pintype "passive"))
      (node (ref "U7") (pin "7") (pinfunction "PGND_7") (pintype "passive"))
      (node (ref "U7") (pin "8") (pinfunction "SW_8") (pintype "passive"))
      (node (ref "U7") (pin "9") (pinfunction "VBAT_9") (pintype "passive"))
      (node (ref "U8") (pin "1") (pinfunction "DACLN_1") (pintype "passive"))
      (node (ref "U8") (pin "10") (pinfunction "VBAT_10") (pintype "passive"))
      (node (ref "U8") (pin "11") (pinfunction "VPWR(PP0)_11") (pintype "passive"))
      (node (ref "U8") (pin "12") (pinfunction "IOVDD_12") (pintype "passive"))
      (node (ref "U8") (pin "13") (pinfunction "DCVDD_13") (pintype "passive"))
      (node (ref "U8") (pin "14") (pinfunction "PB5_14") (pintype "passive"))
      (node (ref "U8") (pin "15") (pinfunction "PB4_15") (pintype "passive"))
      (node (ref "U8") (pin "16") (pinfunction "PB1_16") (pintype "passive"))
      (node (ref "U8") (pin "17") (pinfunction "BTRF_17") (pintype "passive"))
      (node (ref "U8") (pin "18") (pinfunction "XOSCI_18") (pintype "passive"))
      (node (ref "U8") (pin "19") (pinfunction "XOSCO_19") (pintype "passive"))
      (node (ref "U8") (pin "2") (pinfunction "DACLP_2") (pintype "passive"))
      (node (ref "U8") (pin "20") (pinfunction "PC5_20") (pintype "passive"))
      (node (ref "U8") (pin "21") (pinfunction "PC4_21") (pintype "passive"))
      (node (ref "U8") (pin "22") (pinfunction "PC3_22") (pintype "passive"))
      (node (ref "U8") (pin "23") (pinfunction "USBDM_23") (pintype "passive"))
      (node (ref "U8") (pin "24") (pinfunction "USBDP_24") (pintype "passive"))
      (node (ref "U8") (pin "25") (pinfunction "PA4_25") (pintype "passive"))
      (node (ref "U8") (pin "26") (pinfunction "PA3_26") (pintype "passive"))
      (node (ref "U8") (pin "27") (pinfunction "PA2_27") (pintype "passive"))
      (node (ref "U8") (pin "28") (pinfunction "PA1_28") (pintype "passive"))
      (node (ref "U8") (pin "29") (pinfunction "PA0_29") (pintype "passive"))
      (node (ref "U8") (pin "3") (pinfunction "HPVDD_3") (pintype "passive"))
      (node (ref "U8") (pin "30") (pinfunction "ACM_30") (pintype "passive"))
      (node (ref "U8") (pin "31") (pinfunction "VCM_31") (pintype "passive"))
      (node (ref "U8") (pin "32") (pinfunction "AVSS_32") (pintype "passive"))
      (node (ref "U8") (pin "33") (pinfunction "VSS_33") (pintype "passive"))
      (node (ref "U8") (pin "4") (pinfunction "PE6/PG8_4") (pintype "passive"))
      (node (ref "U8") (pin "5") (pinfunction "PG7_5") (pintype "passive"))
      (node (ref "U8") (pin "6") (pinfunction "PG6_6") (pintype "passive"))
      (node (ref "U8") (pin "7") (pinfunction "PG5_7") (pintype "passive"))
      (node (ref "U8") (pin "8") (pinfunction "PGND_8") (pintype "passive"))
      (node (ref "U8") (pin "9") (pinfunction "SW_9") (pintype "passive"))
      (node (ref "U9") (pin "1") (pinfunction "DACRN_1") (pintype "passive"))
      (node (ref "U9") (pin "10") (pinfunction "PG5_10") (pintype "passive"))
      (node (ref "U9") (pin "11") (pinfunction "PGND_11") (pintype "passive"))
      (node (ref "U9") (pin "12") (pinfunction "SW_12") (pintype "passive"))
      (node (ref "U9") (pin "13") (pinfunction "VBAT_13") (pintype "passive"))
      (node (ref "U9") (pin "14") (pinfunction "VPWR_14") (pintype "passive"))
      (node (ref "U9") (pin "15") (pinfunction "IOVDD_15") (pintype "passive"))
      (node (ref "U9") (pin "16") (pinfunction "DCVDD_16") (pintype "passive"))
      (node (ref "U9") (pin "17") (pinfunction "PB8/PB5_17") (pintype "passive"))
      (node (ref "U9") (pin "18") (pinfunction "PB4_18") (pintype "passive"))
      (node (ref "U9") (pin "19") (pinfunction "PB2_19") (pintype "passive"))
      (node (ref "U9") (pin "2") (pinfunction "DACRP_2") (pintype "passive"))
      (node (ref "U9") (pin "20") (pinfunction "PB1_20") (pintype "passive"))
      (node (ref "U9") (pin "21") (pinfunction "BTRF_21") (pintype "passive"))
      (node (ref "U9") (pin "22") (pinfunction "XOSCI_22") (pintype "passive"))
      (node (ref "U9") (pin "23") (pinfunction "XOSCO_23") (pintype "passive"))
      (node (ref "U9") (pin "24") (pinfunction "PC5_24") (pintype "passive"))
      (node (ref "U9") (pin "25") (pinfunction "PC4_25") (pintype "passive"))
      (node (ref "U9") (pin "26") (pinfunction "PC3_26") (pintype "passive"))
      (node (ref "U9") (pin "27") (pinfunction "PC2_27") (pintype "passive"))
      (node (ref "U9") (pin "28") (pinfunction "PC1_28") (pintype "passive"))
      (node (ref "U9") (pin "29") (pinfunction "USBDM_29") (pintype "passive"))
      (node (ref "U9") (pin "3") (pinfunction "DACLN_3") (pintype "passive"))
      (node (ref "U9") (pin "30") (pinfunction "USBDP_30") (pintype "passive"))
      (node (ref "U9") (pin "31") (pinfunction "PA6_31") (pintype "passive"))
      (node (ref "U9") (pin "32") (pinfunction "PA5_32") (pintype "passive"))
      (node (ref "U9") (pin "33") (pinfunction "PA4_33") (pintype "passive"))
      (node (ref "U9") (pin "34") (pinfunction "PA3_34") (pintype "passive"))
      (node (ref "U9") (pin "35") (pinfunction "PA2_35") (pintype "passive"))
      (node (ref "U9") (pin "36") (pinfunction "PA1_36") (pintype "passive"))
      (node (ref "U9") (pin "37") (pinfunction "PA0_37") (pintype "passive"))
      (node (ref "U9") (pin "38") (pinfunction "ACM_38") (pintype "passive"))
      (node (ref "U9") (pin "39") (pinfunction "AVSS_39") (pintype "passive"))
      (node (ref "U9") (pin "4") (pinfunction "DACLP_4") (pintype "passive"))
      (node (ref "U9") (pin "40") (pinfunction "VCM_40") (pintype "passive"))
      (node (ref "U9") (pin "5") (pinfunction "HPVDD_5") (pintype "passive"))
      (node (ref "U9") (pin "6") (pinfunction "PE6/PE5_6") (pintype "passive"))
      (node (ref "U9") (pin "7") (pinfunction "PG8_7") (pintype "passive"))
      (node (ref "U9") (pin "8") (pinfunction "PG7_8") (pintype "passive"))
      (node (ref "U9") (pin "9") (pinfunction "PG6_9") (pintype "passive"))
    )
    (net (code "4") (name "Net-(ANT4-Pad3)") (class "Default")
      (node (ref "ANT4") (pin "3") (pinfunction "3_3") (pintype "passive"))
      (node (ref "C61") (pin "2") (pinfunction "2_2") (pintype "passive"))
    )
    (net (code "5") (name "Net-(ANT5-Pad3)") (class "Default")
      (node (ref "ANT5") (pin "3") (pinfunction "3_3") (pintype "passive"))
      (node (ref "C62") (pin "2") (pinfunction "2_2") (pintype "passive"))
    )
    (net (code "6") (name "Net-(C57-Pad2)") (class "Default")
      (node (ref "C57") (pin "2") (pinfunction "2_2") (pintype "passive"))
      (node (ref "U4") (pin "3") (pinfunction "3_3") (pintype "passive"))
    )
    (net (code "7") (name "Net-(C58-Pad2)") (class "Default")
      (node (ref "C58") (pin "2") (pinfunction "2_2") (pintype "passive"))
      (node (ref "U10") (pin "3") (pinfunction "3_3") (pintype "passive"))
    )
    (net (code "8") (name "Net-(C59-Pad2)") (class "Default")
      (node (ref "C59") (pin "2") (pinfunction "2_2") (pintype "passive"))
      (node (ref "L28") (pin "3") (pinfunction "3_3") (pintype "passive"))
    )
    (net (code "9") (name "Net-(C60-Pad2)") (class "Default")
      (node (ref "C60") (pin "2") (pinfunction "2_2") (pintype "passive"))
      (node (ref "L29") (pin "3") (pinfunction "3_3") (pintype "passive"))
    )
    (net (code "10") (name "Net-(J4-Pad01)") (class "Default")
      (node (ref "J4") (pin "01") (pinfunction "01_01") (pintype "passive"))
      (node (ref "R24") (pin "2") (pinfunction "2_2") (pintype "passive"))
    )
    (net (code "11") (name "Net-(J4-Pad02)") (class "Default")
      (node (ref "J4") (pin "02") (pinfunction "02_02") (pintype "passive"))
      (node (ref "R25") (pin "2") (pinfunction "2_2") (pintype "passive"))
    )
    (net (code "12") (name "Net-(J4-Pad03)") (class "Default")
      (node (ref "J4") (pin "03") (pinfunction "03_03") (pintype "passive"))
      (node (ref "R26") (pin "2") (pinfunction "2_2") (pintype "passive"))
    )
    (net (code "13") (name "Net-(J4-Pad04)") (class "Default")
      (node (ref "J4") (pin "04") (pinfunction "04_04") (pintype "passive"))
      (node (ref "R27") (pin "2") (pinfunction "2_2") (pintype "passive"))
    )
    (net (code "14") (name "Net-(J4-Pad05)") (class "Default")
      (node (ref "J4") (pin "05") (pinfunction "05_05") (pintype "passive"))
      (node (ref "R28") (pin "2") (pinfunction "2_2") (pintype "passive"))
    )
    (net (code "15") (name "Net-(J4-Pad07)") (class "Default")
      (node (ref "J4") (pin "07") (pinfunction "07_07") (pintype "passive"))
      (node (ref "R29") (pin "2") (pinfunction "2_2") (pintype "passive"))
    )
    (net (code "16") (name "Net-(LED7-A)") (class "Default")
      (node (ref "LED7") (pin "2") (pinfunction "A_2") (pintype "passive"))
      (node (ref "R24") (pin "1") (pinfunction "1_1") (pintype "passive"))
    )
    (net (code "17") (name "Net-(LED8-A)") (class "Default")
      (node (ref "LED8") (pin "1") (pinfunction "A_1") (pintype "passive"))
      (node (ref "R25") (pin "1") (pinfunction "1_1") (pintype "passive"))
    )
    (net (code "18") (name "Net-(LED9-A)") (class "Default")
      (node (ref "LED9") (pin "2") (pinfunction "A_2") (pintype "passive"))
      (node (ref "R26") (pin "1") (pinfunction "1_1") (pintype "passive"))
    )
    (net (code "19") (name "Net-(LED10-A)") (class "Default")
      (node (ref "LED10") (pin "2") (pinfunction "A_2") (pintype "passive"))
      (node (ref "R27") (pin "1") (pinfunction "1_1") (pintype "passive"))
    )
    (net (code "20") (name "Net-(LED11-+)") (class "Default")
      (node (ref "LED11") (pin "2") (pinfunction "+_2") (pintype "passive"))
      (node (ref "R28") (pin "1") (pinfunction "1_1") (pintype "passive"))
    )
    (net (code "21") (name "unconnected-(ANT4-Pad1)") (class "Default")
      (node (ref "ANT4") (pin "1") (pinfunction "1_1") (pintype "passive"))
    )
    (net (code "22") (name "unconnected-(ANT4-Pad2)") (class "Default")
      (node (ref "ANT4") (pin "2") (pinfunction "2_2") (pintype "passive"))
    )
    (net (code "23") (name "unconnected-(ANT5-Pad1)") (class "Default")
      (node (ref "ANT5") (pin "1") (pinfunction "1_1") (pintype "passive"))
    )
    (net (code "24") (name "unconnected-(ANT5-Pad2)") (class "Default")
      (node (ref "ANT5") (pin "2") (pinfunction "2_2") (pintype "passive"))
    )
    (net (code "25") (name "unconnected-(L28-NC-Pad2)") (class "Default")
      (node (ref "L28") (pin "2") (pinfunction "NC_2") (pintype "passive"))
    )
    (net (code "26") (name "unconnected-(L28-Pad1)") (class "Default")
      (node (ref "L28") (pin "1") (pinfunction "1_1") (pintype "passive"))
    )
    (net (code "27") (name "unconnected-(L29-NC-Pad2)") (class "Default")
      (node (ref "L29") (pin "2") (pinfunction "NC_2") (pintype "passive"))
    )
    (net (code "28") (name "unconnected-(L29-Pad1)") (class "Default")
      (node (ref "L29") (pin "1") (pinfunction "1_1") (pintype "passive"))
    )
    (net (code "29") (name "unconnected-(U4-Pad1)") (class "Default")
      (node (ref "U4") (pin "1") (pinfunction "1_1") (pintype "passive"))
    )
    (net (code "30") (name "unconnected-(U4-Pad2)") (class "Default")
      (node (ref "U4") (pin "2") (pinfunction "2_2") (pintype "passive"))
    )
    (net (code "31") (name "unconnected-(U7-VSS-Pad33)") (class "Default")
      (node (ref "U7") (pin "33") (pinfunction "VSS_33") (pintype "passive"))
    )
    (net (code "32") (name "unconnected-(U9-VSS-Pad41)") (class "Default")
      (node (ref "U9") (pin "41") (pinfunction "VSS_41") (pintype "passive"))
    )
    (net (code "33") (name "unconnected-(U10-Pad1)") (class "Default")
      (node (ref "U10") (pin "1") (pinfunction "1_1") (pintype "passive"))
    )
    (net (code "34") (name "unconnected-(U10-Pad2)") (class "Default")
      (node (ref "U10") (pin "2") (pinfunction "2_2") (pintype "passive"))
    )
  )
)
